# ProPrj_cbadge_2025-11-28.net
KiCad netlist of a schematic drawn in EasyEDA Pro
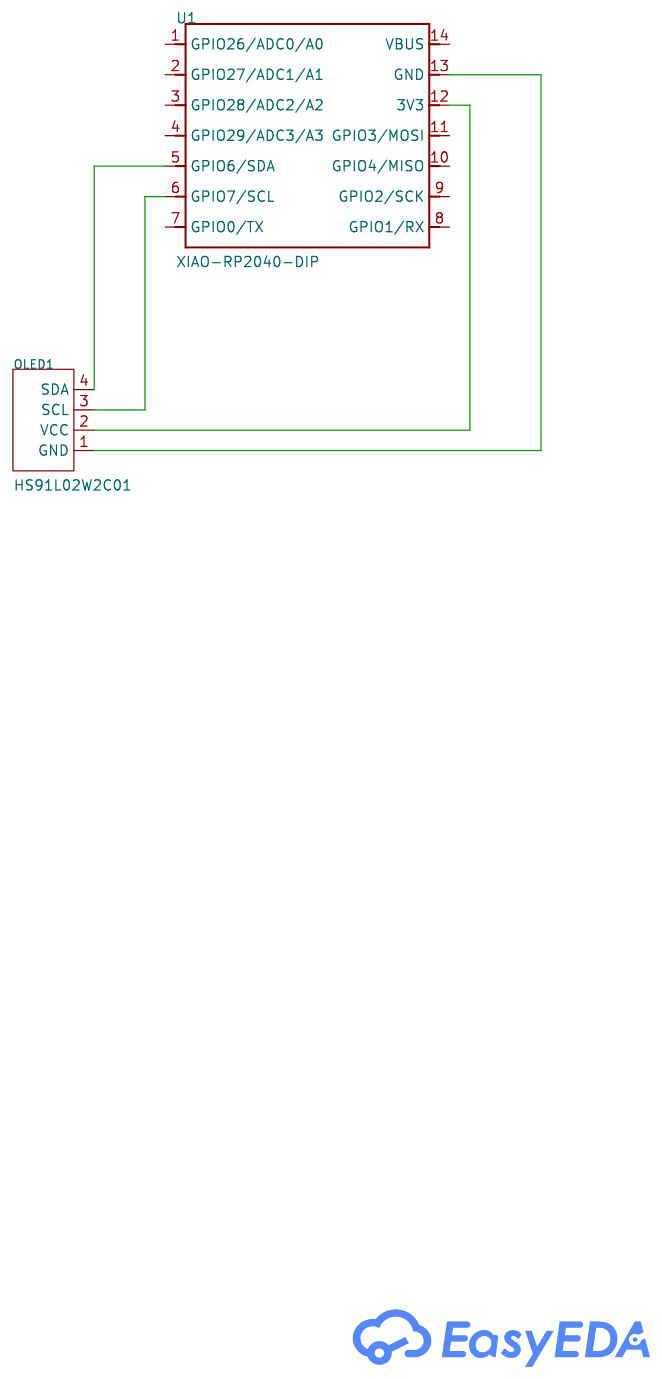
[diagram p0: schematic sheet]

(export (version "E")
  (design (tool "Eeschema 10.0.6"))
  (components
    (comp (ref "OLED1")
      (value "HS91L02W2C01")
      (footprint "easyedapro:OLED-TH_L38.0-W12.0_HS91L02W2C01")
      (fields (field (name "Manufacturer") "HS(汉昇)"))
      (libsource (lib "easyedapro") (part "HS91L02W2C01"))
    )
    (comp (ref "U1") (value "XIAO-RP2040-DIP") (libsource (lib "easyedapro") (part "XIAO-RP2040-DIP")))
  )
  (nets
    (net (code "1") (name "Net-(OLED1-GND)") (class "Default")
      (node (ref "OLED1") (pin "1") (pinfunction "GND_1") (pintype "input"))
      (node (ref "U1") (pin "13") (pinfunction "GND_13") (pintype "unspecified"))
    )
    (net (code "2") (name "Net-(OLED1-SCL)") (class "Default")
      (node (ref "OLED1") (pin "3") (pinfunction "SCL_3") (pintype "input"))
      (node (ref "U1") (pin "6") (pinfunction "GPIO7/SCL_6") (pintype "unspecified"))
    )
    (net (code "3") (name "Net-(OLED1-SDA)") (class "Default")
      (node (ref "OLED1") (pin "4") (pinfunction "SDA_4") (pintype "input"))
      (node (ref "U1") (pin "5") (pinfunction "GPIO6/SDA_5") (pintype "unspecified"))
    )
    (net (code "4") (name "Net-(OLED1-VCC)") (class "Default")
      (node (ref "OLED1") (pin "2") (pinfunction "VCC_2") (pintype "input"))
      (node (ref "U1") (pin "12") (pinfunction "3V3_12") (pintype "unspecified"))
    )
    (net (code "5") (name "unconnected-(U1-GPIO0{slash}TX-Pad7)") (class "Default")
      (node (ref "U1") (pin "7") (pinfunction "GPIO0/TX_7") (pintype "unspecified"))
    )
    (net (code "6") (name "unconnected-(U1-GPIO1{slash}RX-Pad8)") (class "Default")
      (node (ref "U1") (pin "8") (pinfunction "GPIO1/RX_8") (pintype "unspecified"))
    )
    (net (code "7") (name "unconnected-(U1-GPIO2{slash}SCK-Pad9)") (class "Default")
      (node (ref "U1") (pin "9") (pinfunction "GPIO2/SCK_9") (pintype "unspecified"))
    )
    (net (code "8") (name "unconnected-(U1-GPIO3{slash}MOSI-Pad11)") (class "Default")
      (node (ref "U1") (pin "11") (pinfunction "GPIO3/MOSI_11") (pintype "unspecified"))
    )
    (net (code "9") (name "unconnected-(U1-GPIO4{slash}MISO-Pad10)") (class "Default")
      (node (ref "U1") (pin "10") (pinfunction "GPIO4/MISO_10") (pintype "unspecified"))
    )
    (net (code "10") (name "unconnected-(U1-GPIO26{slash}ADC0{slash}A0-Pad1)") (class "Default")
      (node (ref "U1") (pin "1") (pinfunction "GPIO26/ADC0/A0_1") (pintype "unspecified"))
    )
    (net (code "11") (name "unconnected-(U1-GPIO27{slash}ADC1{slash}A1-Pad2)") (class "Default")
      (node (ref "U1") (pin "2") (pinfunction "GPIO27/ADC1/A1_2") (pintype "unspecified"))
    )
    (net (code "12") (name "unconnected-(U1-GPIO28{slash}ADC2{slash}A2-Pad3)") (class "Default")
      (node (ref "U1") (pin "3") (pinfunction "GPIO28/ADC2/A2_3") (pintype "unspecified"))
    )
    (net (code "13") (name "unconnected-(U1-GPIO29{slash}ADC3{slash}A3-Pad4)") (class "Default")
      (node (ref "U1") (pin "4") (pinfunction "GPIO29/ADC3/A3_4") (pintype "unspecified"))
    )
    (net (code "14") (name "unconnected-(U1-VBUS-Pad14)") (class "Default")
      (node (ref "U1") (pin "14") (pinfunction "VBUS_14") (pintype "unspecified"))
    )
  )
)
